# Sheet1.net
KiCad netlist of a schematic drawn in Altium Designer
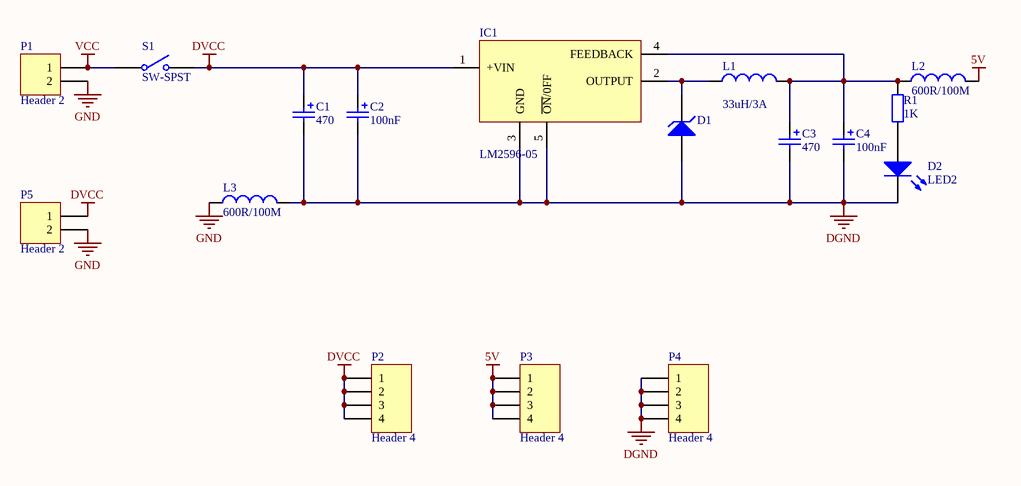
[diagram p0: Sheet1.SchDoc]

(export (version "E")
  (design (tool "Eeschema 10.0.6"))
  (components
    (comp (ref "C1")
      (value "470")
      (footprint "ccc")
      (description "Polarized Capacitor (Axial)")
      (fields (field (name "PUBLISHER") "Altium Limited"))
      (libsource (lib "Miscellaneous Devices") (part "Cap Pol2"))
    )
    (comp (ref "C2")
      (value "100nF")
      (footprint "C0805")
      (description "Polarized Capacitor (Axial)")
      (fields (field (name "PUBLISHER") "Altium Limited"))
      (libsource (lib "Miscellaneous Devices") (part "Cap Pol2"))
    )
    (comp (ref "C3")
      (value "470")
      (footprint "ccc")
      (description "Polarized Capacitor (Axial)")
      (fields (field (name "PUBLISHER") "Altium Limited"))
      (libsource (lib "Miscellaneous Devices") (part "Cap Pol2"))
    )
    (comp (ref "C4")
      (value "100nF")
      (footprint "C0805")
      (description "Polarized Capacitor (Axial)")
      (fields (field (name "PUBLISHER") "Altium Limited"))
      (libsource (lib "Miscellaneous Devices") (part "Cap Pol2"))
    )
    (comp (ref "D1")
      (value "D Zener")
      (footprint "D1810")
      (description "Zener Diode")
      (fields (field (name "PUBLISHER") "Altium Limited"))
      (libsource (lib "Miscellaneous Devices") (part "D Zener"))
    )
    (comp (ref "D2")
      (value "LED2")
      (footprint "D0805")
      (description "Typical RED, GREEN, YELLOW, AMBER GaAs LED")
      (fields (field (name "PUBLISHER") "Altium Limited"))
      (libsource (lib "Miscellaneous Devices") (part "LED2"))
    )
    (comp (ref "IC1")
      (value "LM2596-05")
      (footprint "TO-263-5")
      (libsource (lib "飞思卡尔元件库") (part "LM2596-05"))
    )
    (comp (ref "L1")
      (value "33uH/3A")
      (footprint "L-12*12MM-S")
      (description "Inductor")
      (fields (field (name "PUBLISHER") "Altium Limited"))
      (libsource (lib "Miscellaneous Devices") (part "Inductor"))
    )
    (comp (ref "L2")
      (value "600R/100M")
      (footprint "L1206")
      (description "Inductor")
      (fields (field (name "PUBLISHER") "Altium Limited"))
      (libsource (lib "Miscellaneous Devices") (part "Inductor"))
    )
    (comp (ref "L3")
      (value "600R/100M")
      (footprint "L1206")
      (description "Inductor")
      (fields (field (name "PUBLISHER") "Altium Limited"))
      (libsource (lib "Miscellaneous Devices") (part "Inductor"))
    )
    (comp (ref "P1")
      (value "Header 2")
      (footprint "SIP2-1")
      (description "Header, 2-Pin")
      (fields (field (name "PUBLISHER") "Altium Limited"))
      (libsource (lib "Miscellaneous Connectors") (part "Header 2"))
    )
    (comp (ref "P2")
      (value "Header 4")
      (footprint "HDR1X4")
      (description "Header, 4-Pin")
      (fields (field (name "PUBLISHER") "Altium Limited"))
      (libsource (lib "Miscellaneous Connectors") (part "Header 4"))
    )
    (comp (ref "P3")
      (value "Header 4")
      (footprint "HDR1X4")
      (description "Header, 4-Pin")
      (fields (field (name "PUBLISHER") "Altium Limited"))
      (libsource (lib "Miscellaneous Connectors") (part "Header 4"))
    )
    (comp (ref "P4")
      (value "Header 4")
      (footprint "HDR1X4")
      (description "Header, 4-Pin")
      (fields (field (name "PUBLISHER") "Altium Limited"))
      (libsource (lib "Miscellaneous Connectors") (part "Header 4"))
    )
    (comp (ref "P5")
      (value "Header 2")
      (footprint "SIP2-1")
      (description "Header, 2-Pin")
      (fields (field (name "PUBLISHER") "Altium Limited"))
      (libsource (lib "Miscellaneous Connectors") (part "Header 2"))
    )
    (comp (ref "R1")
      (value "1K")
      (footprint "R0805")
      (description "Resistor")
      (fields (field (name "Comment") "Res2") (field (name "PUBLISHER") "Altium Limited"))
      (libsource (lib "Miscellaneous Devices") (part "Res2"))
    )
    (comp (ref "S1")
      (value "SW-SPST")
      (footprint "PCBComponent_1")
      (description "Single-Pole, Single-Throw Switch")
      (fields (field (name "PUBLISHER") "Altium Limited"))
      (libsource (lib "Miscellaneous Devices") (part "SW-SPST"))
    )
  )
  (nets
    (net (code "1") (name "5V") (class "Default")
      (node (ref "L2") (pin "2") (pinfunction "2_2") (pintype "passive"))
      (node (ref "P3") (pin "1") (pinfunction "1_1") (pintype "passive"))
      (node (ref "P3") (pin "2") (pinfunction "2_2") (pintype "passive"))
      (node (ref "P3") (pin "3") (pinfunction "3_3") (pintype "passive"))
      (node (ref "P3") (pin "4") (pinfunction "4_4") (pintype "passive"))
    )
    (net (code "2") (name "DGND") (class "Default")
      (node (ref "C1") (pin "2") (pinfunction "2_2") (pintype "passive"))
      (node (ref "C2") (pin "2") (pinfunction "2_2") (pintype "passive"))
      (node (ref "C3") (pin "2") (pinfunction "2_2") (pintype "passive"))
      (node (ref "C4") (pin "2") (pinfunction "2_2") (pintype "passive"))
      (node (ref "D1") (pin "1") (pinfunction "A_1") (pintype "passive"))
      (node (ref "D2") (pin "2") (pinfunction "K_2") (pintype "passive"))
      (node (ref "IC1") (pin "3") (pinfunction "GND_3") (pintype "passive"))
      (node (ref "IC1") (pin "5") (pinfunction "~{ON}/0FF_5") (pintype "passive"))
      (node (ref "L3") (pin "2") (pinfunction "2_2") (pintype "passive"))
      (node (ref "P4") (pin "1") (pinfunction "1_1") (pintype "passive"))
      (node (ref "P4") (pin "2") (pinfunction "2_2") (pintype "passive"))
      (node (ref "P4") (pin "3") (pinfunction "3_3") (pintype "passive"))
      (node (ref "P4") (pin "4") (pinfunction "4_4") (pintype "passive"))
    )
    (net (code "3") (name "DVCC") (class "Default")
      (node (ref "C1") (pin "1") (pinfunction "1_1") (pintype "passive"))
      (node (ref "C2") (pin "1") (pinfunction "1_1") (pintype "passive"))
      (node (ref "IC1") (pin "1") (pinfunction "+VIN_1") (pintype "passive"))
      (node (ref "P2") (pin "1") (pinfunction "1_1") (pintype "passive"))
      (node (ref "P2") (pin "2") (pinfunction "2_2") (pintype "passive"))
      (node (ref "P2") (pin "3") (pinfunction "3_3") (pintype "passive"))
      (node (ref "P2") (pin "4") (pinfunction "4_4") (pintype "passive"))
      (node (ref "P5") (pin "1") (pinfunction "1_1") (pintype "passive"))
      (node (ref "S1") (pin "2") (pinfunction "NO_2") (pintype "passive"))
    )
    (net (code "4") (name "GND") (class "Default")
      (node (ref "L3") (pin "1") (pinfunction "1_1") (pintype "passive"))
      (node (ref "P1") (pin "2") (pinfunction "2_2") (pintype "passive"))
      (node (ref "P5") (pin "2") (pinfunction "2_2") (pintype "passive"))
    )
    (net (code "5") (name "Net-(D1-K)") (class "Default")
      (node (ref "D1") (pin "2") (pinfunction "K_2") (pintype "passive"))
      (node (ref "IC1") (pin "2") (pinfunction "OUTPUT_2") (pintype "passive"))
      (node (ref "L1") (pin "1") (pinfunction "1_1") (pintype "passive"))
    )
    (net (code "6") (name "Net-(D2-A)") (class "Default")
      (node (ref "D2") (pin "1") (pinfunction "A_1") (pintype "passive"))
      (node (ref "R1") (pin "2") (pinfunction "2_2") (pintype "passive"))
    )
    (net (code "7") (name "Net-(IC1-FEEDBACK)") (class "Default")
      (node (ref "C3") (pin "1") (pinfunction "1_1") (pintype "passive"))
      (node (ref "C4") (pin "1") (pinfunction "1_1") (pintype "passive"))
      (node (ref "IC1") (pin "4") (pinfunction "FEEDBACK_4") (pintype "passive"))
      (node (ref "L1") (pin "2") (pinfunction "2_2") (pintype "passive"))
      (node (ref "L2") (pin "1") (pinfunction "1_1") (pintype "passive"))
      (node (ref "R1") (pin "1") (pinfunction "1_1") (pintype "passive"))
    )
    (net (code "8") (name "VCC") (class "Default")
      (node (ref "P1") (pin "1") (pinfunction "1_1") (pintype "passive"))
      (node (ref "S1") (pin "1") (pinfunction "COMMON_1") (pintype "passive"))
    )
  )
)
